# PLD_RadFET_Supply.net
KiCad netlist of a schematic drawn in Altium Designer
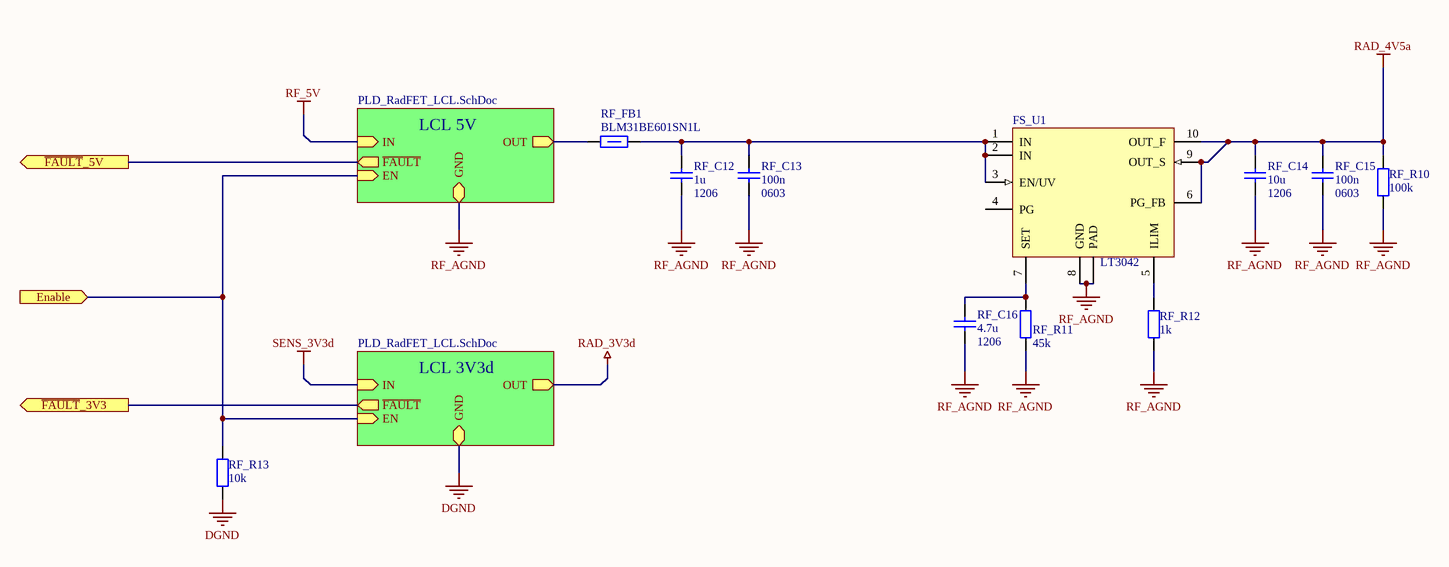
[diagram p0: PLD_RadFET_Supply.SchDoc]

(export (version "E")
  (design (tool "Eeschema 10.0.6"))
  (components
    (comp (ref "FS_U1")
      (value "LT3042")
      (footprint "MSOP-10-M-thermal-pad")
      (description "20V, 200mA, Ultralow Noise, Ultrahigh PSRR RF Linear Regulator")
      (libsource (lib "microcircuits") (part "LT3042"))
    )
    (comp (ref "RF_C12")
      (value "1u")
      (footprint "SMD_Capacitor_1206")
      (description "Cap")
      (fields (field (name "PACKAGE") "1206"))
      (libsource (lib "capacitors") (part "Cap"))
    )
    (comp (ref "RF_C13")
      (value "100n")
      (footprint "SMD_Capacitor_0603")
      (description "Cap")
      (fields (field (name "PACKAGE") "0603"))
      (libsource (lib "capacitors") (part "Cap"))
    )
    (comp (ref "RF_C14")
      (value "10u")
      (footprint "SMD_Capacitor_1206")
      (description "Cap")
      (fields (field (name "PACKAGE") "1206"))
      (libsource (lib "capacitors") (part "Cap"))
    )
    (comp (ref "RF_C15")
      (value "100n")
      (footprint "SMD_Capacitor_0603")
      (description "Cap")
      (fields (field (name "PACKAGE") "0603"))
      (libsource (lib "capacitors") (part "Cap"))
    )
    (comp (ref "RF_C16")
      (value "4.7u")
      (footprint "SMD_Capacitor_1206")
      (description "Cap")
      (fields (field (name "PACKAGE") "1206"))
      (libsource (lib "capacitors") (part "Cap"))
    )
    (comp (ref "RF_FB1")
      (value "600R/100MHz")
      (footprint "1206")
      (description "Ferrite Bead")
      (fields (field (name "MANUFACTURER") "Murata") (field (name "MANUFACTURERPARTNUMBER") "BLM31BE601SN1L"))
      (libsource (lib "inductors") (part "FerriteBead"))
    )
    (comp (ref "RF_R10")
      (value "100k")
      (footprint "SMD_Resistor_0603")
      (libsource (lib "resistors") (part "Res"))
    )
    (comp (ref "RF_R11")
      (value "45k")
      (footprint "SMD_Resistor_0603")
      (libsource (lib "resistors") (part "Res"))
    )
    (comp (ref "RF_R12")
      (value "1k")
      (footprint "SMD_Resistor_0603")
      (libsource (lib "resistors") (part "Res"))
    )
    (comp (ref "RF_R13")
      (value "10k")
      (footprint "SMD_Resistor_0603")
      (libsource (lib "resistors") (part "Res"))
    )
  )
  (nets
    (net (code "1") (name "/Enable") (class "Default")
      (node (ref "RF_R13") (pin "2") (pinfunction "2_2") (pintype "passive"))
    )
    (net (code "2") (name "/OUT") (class "Default")
      (node (ref "RF_FB1") (pin "2") (pinfunction "2_2") (pintype "passive"))
    )
    (net (code "5") (name "DGND") (class "Default")
      (node (ref "RF_R13") (pin "1") (pinfunction "1_1") (pintype "passive"))
    )
    (net (code "6") (name "Net-(FS_U1-EN{slash}UV)") (class "Default")
      (node (ref "FS_U1") (pin "1") (pinfunction "IN_1") (pintype "power_in"))
      (node (ref "FS_U1") (pin "2") (pinfunction "IN_2") (pintype "power_in"))
      (node (ref "FS_U1") (pin "3") (pinfunction "EN/UV_3") (pintype "input"))
      (node (ref "RF_C12") (pin "1") (pinfunction "1_1") (pintype "passive"))
      (node (ref "RF_C13") (pin "1") (pinfunction "1_1") (pintype "passive"))
      (node (ref "RF_FB1") (pin "1") (pinfunction "1_1") (pintype "passive"))
    )
    (net (code "7") (name "Net-(FS_U1-ILIM)") (class "Default")
      (node (ref "FS_U1") (pin "5") (pinfunction "ILIM_5") (pintype "passive"))
      (node (ref "RF_R12") (pin "2") (pinfunction "2_2") (pintype "passive"))
    )
    (net (code "8") (name "Net-(FS_U1-SET)") (class "Default")
      (node (ref "FS_U1") (pin "7") (pinfunction "SET_7") (pintype "passive"))
      (node (ref "RF_C16") (pin "1") (pinfunction "1_1") (pintype "passive"))
      (node (ref "RF_R11") (pin "2") (pinfunction "2_2") (pintype "passive"))
    )
    (net (code "10") (name "RAD_4V5a") (class "Default")
      (node (ref "FS_U1") (pin "10") (pinfunction "OUT_F_10") (pintype "power_in"))
      (node (ref "FS_U1") (pin "6") (pinfunction "PG_FB_6") (pintype "passive"))
      (node (ref "FS_U1") (pin "9") (pinfunction "OUT_S_9") (pintype "input"))
      (node (ref "RF_C14") (pin "1") (pinfunction "1_1") (pintype "passive"))
      (node (ref "RF_C15") (pin "1") (pinfunction "1_1") (pintype "passive"))
      (node (ref "RF_R10") (pin "2") (pinfunction "2_2") (pintype "passive"))
    )
    (net (code "12") (name "RF_AGND") (class "Default")
      (node (ref "FS_U1") (pin "11") (pinfunction "PAD_11") (pintype "power_in"))
      (node (ref "FS_U1") (pin "8") (pinfunction "GND_8") (pintype "power_in"))
      (node (ref "RF_C12") (pin "2") (pinfunction "2_2") (pintype "passive"))
      (node (ref "RF_C13") (pin "2") (pinfunction "2_2") (pintype "passive"))
      (node (ref "RF_C14") (pin "2") (pinfunction "2_2") (pintype "passive"))
      (node (ref "RF_C15") (pin "2") (pinfunction "2_2") (pintype "passive"))
      (node (ref "RF_C16") (pin "2") (pinfunction "2_2") (pintype "passive"))
      (node (ref "RF_R10") (pin "1") (pinfunction "1_1") (pintype "passive"))
      (node (ref "RF_R11") (pin "1") (pinfunction "1_1") (pintype "passive"))
      (node (ref "RF_R12") (pin "1") (pinfunction "1_1") (pintype "passive"))
    )
    (net (code "14") (name "unconnected-(FS_U1-PG-Pad4)") (class "Default")
      (node (ref "FS_U1") (pin "4") (pinfunction "PG_4") (pintype "power_in"))
    )
  )
)
